# line_sensor.net
KiCad netlist of a schematic drawn in EAGLE
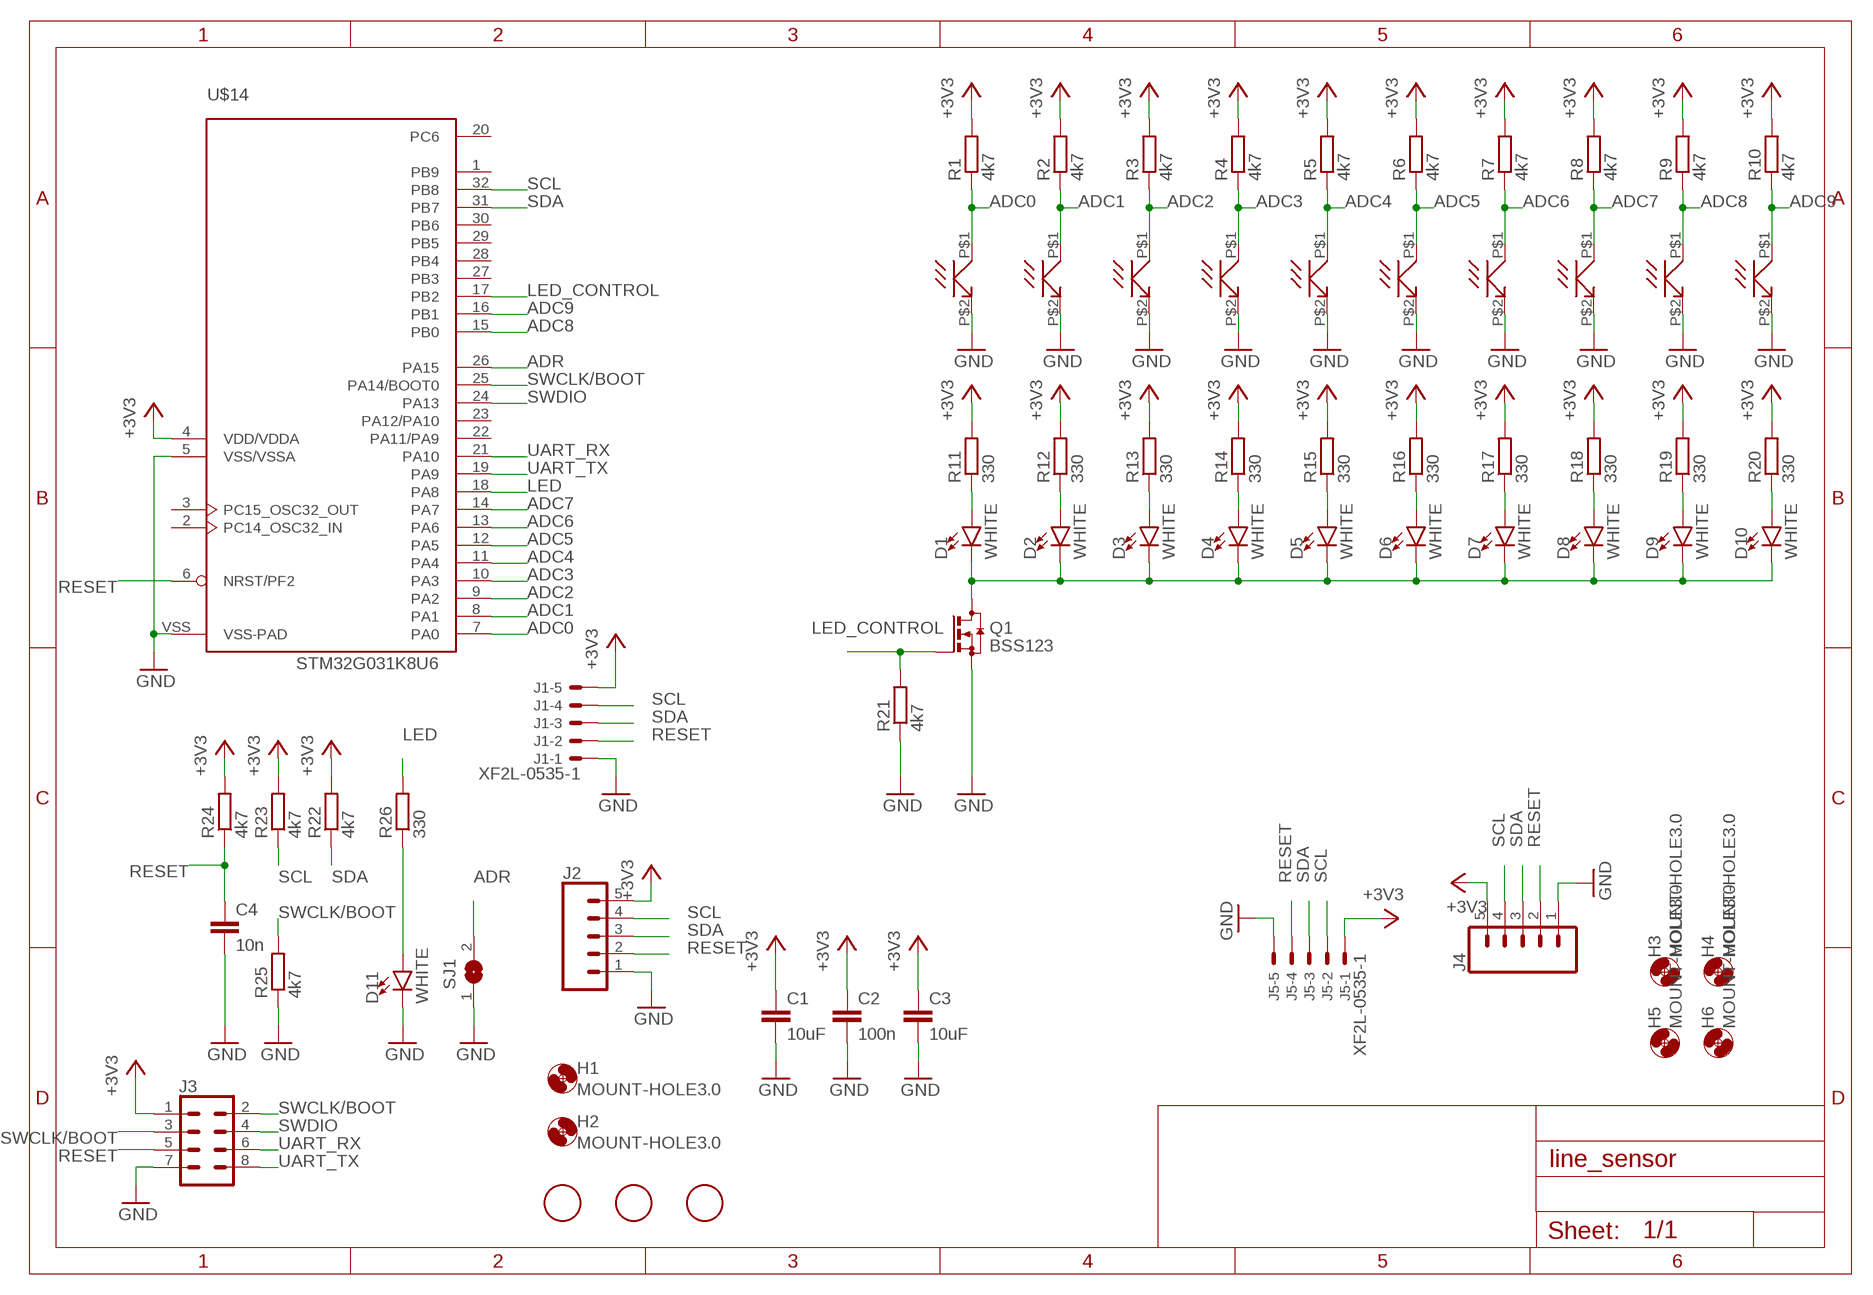
[diagram p0: schematic, sheet 1]

(export (version "E")
  (design (tool "Eeschema 10.0.6"))
  (components
    (comp (ref "C1")
      (value "10uF")
      (footprint "eagle-import:C0805K")
      (libsource (lib "eagle-import") (part "C-EUC0805K"))
    )
    (comp (ref "C2")
      (value "100n")
      (footprint "eagle-import:C0805K")
      (libsource (lib "eagle-import") (part "C-EUC0805K"))
    )
    (comp (ref "C3")
      (value "10uF")
      (footprint "eagle-import:C0805K")
      (libsource (lib "eagle-import") (part "C-EUC0805K"))
    )
    (comp (ref "C4")
      (value "10n")
      (footprint "eagle-import:C0805K")
      (libsource (lib "eagle-import") (part "C-EUC0805K"))
    )
    (comp (ref "D1")
      (value "WHITE")
      (footprint "eagle-import:LED-1206")
      (libsource (lib "eagle-import") (part "LED-WHITE1206"))
    )
    (comp (ref "D2")
      (value "WHITE")
      (footprint "eagle-import:LED-1206")
      (libsource (lib "eagle-import") (part "LED-WHITE1206"))
    )
    (comp (ref "D3")
      (value "WHITE")
      (footprint "eagle-import:LED-1206")
      (libsource (lib "eagle-import") (part "LED-WHITE1206"))
    )
    (comp (ref "D4")
      (value "WHITE")
      (footprint "eagle-import:LED-1206")
      (libsource (lib "eagle-import") (part "LED-WHITE1206"))
    )
    (comp (ref "D5")
      (value "WHITE")
      (footprint "eagle-import:LED-1206")
      (libsource (lib "eagle-import") (part "LED-WHITE1206"))
    )
    (comp (ref "D6")
      (value "WHITE")
      (footprint "eagle-import:LED-1206")
      (libsource (lib "eagle-import") (part "LED-WHITE1206"))
    )
    (comp (ref "D7")
      (value "WHITE")
      (footprint "eagle-import:LED-1206")
      (libsource (lib "eagle-import") (part "LED-WHITE1206"))
    )
    (comp (ref "D8")
      (value "WHITE")
      (footprint "eagle-import:LED-1206")
      (libsource (lib "eagle-import") (part "LED-WHITE1206"))
    )
    (comp (ref "D9")
      (value "WHITE")
      (footprint "eagle-import:LED-1206")
      (libsource (lib "eagle-import") (part "LED-WHITE1206"))
    )
    (comp (ref "D10")
      (value "WHITE")
      (footprint "eagle-import:LED-1206")
      (libsource (lib "eagle-import") (part "LED-WHITE1206"))
    )
    (comp (ref "D11")
      (value "WHITE")
      (footprint "eagle-import:LED-1206")
      (libsource (lib "eagle-import") (part "LED-WHITE1206"))
    )
    (comp (ref "H1")
      (value "MOUNT-HOLE3.0")
      (footprint "eagle-import:3,0")
      (libsource (lib "eagle-import") (part "MOUNT-HOLE3.0"))
    )
    (comp (ref "H2")
      (value "MOUNT-HOLE3.0")
      (footprint "eagle-import:3,0")
      (libsource (lib "eagle-import") (part "MOUNT-HOLE3.0"))
    )
    (comp (ref "H3")
      (value "MOUNT-HOLE3.0")
      (footprint "eagle-import:3,0")
      (libsource (lib "eagle-import") (part "MOUNT-HOLE3.0"))
    )
    (comp (ref "H4")
      (value "MOUNT-HOLE3.0")
      (footprint "eagle-import:3,0")
      (libsource (lib "eagle-import") (part "MOUNT-HOLE3.0"))
    )
    (comp (ref "H5")
      (value "MOUNT-HOLE3.0")
      (footprint "eagle-import:3,0")
      (libsource (lib "eagle-import") (part "MOUNT-HOLE3.0"))
    )
    (comp (ref "H6")
      (value "MOUNT-HOLE3.0")
      (footprint "eagle-import:3,0")
      (libsource (lib "eagle-import") (part "MOUNT-HOLE3.0"))
    )
    (comp (ref "J1")
      (value "XF2L-0535-1")
      (footprint "eagle-import:XF2L-0535-1")
      (fields (field (name "MPN") "XF2L-0535-1A"))
      (libsource (lib "eagle-import") (part "XF2-05?35-1L"))
    )
    (comp (ref "J2")
      (value "CONN_05")
      (footprint "eagle-import:1X05")
      (libsource (lib "eagle-import") (part "CONN_05"))
    )
    (comp (ref "J3")
      (value "CONN_04X2")
      (footprint "eagle-import:2X4")
      (libsource (lib "eagle-import") (part "CONN_04X2"))
    )
    (comp (ref "J4")
      (value "CONN_05")
      (footprint "eagle-import:1X05")
      (libsource (lib "eagle-import") (part "CONN_05"))
    )
    (comp (ref "J5")
      (value "XF2L-0535-1")
      (footprint "eagle-import:XF2L-0535-1")
      (fields (field (name "MPN") "XF2L-0535-1A"))
      (libsource (lib "eagle-import") (part "XF2-05?35-1L"))
    )
    (comp (ref "Q1")
      (value "BSS123")
      (footprint "eagle-import:SOT23")
      (libsource (lib "eagle-import") (part "BSS123"))
    )
    (comp (ref "R1")
      (value "4k7")
      (footprint "eagle-import:M0805")
      (libsource (lib "eagle-import") (part "R-EU_M0805"))
    )
    (comp (ref "R2")
      (value "4k7")
      (footprint "eagle-import:M0805")
      (libsource (lib "eagle-import") (part "R-EU_M0805"))
    )
    (comp (ref "R3")
      (value "4k7")
      (footprint "eagle-import:M0805")
      (libsource (lib "eagle-import") (part "R-EU_M0805"))
    )
    (comp (ref "R4")
      (value "4k7")
      (footprint "eagle-import:M0805")
      (libsource (lib "eagle-import") (part "R-EU_M0805"))
    )
    (comp (ref "R5")
      (value "4k7")
      (footprint "eagle-import:M0805")
      (libsource (lib "eagle-import") (part "R-EU_M0805"))
    )
    (comp (ref "R6")
      (value "4k7")
      (footprint "eagle-import:M0805")
      (libsource (lib "eagle-import") (part "R-EU_M0805"))
    )
    (comp (ref "R7")
      (value "4k7")
      (footprint "eagle-import:M0805")
      (libsource (lib "eagle-import") (part "R-EU_M0805"))
    )
    (comp (ref "R8")
      (value "4k7")
      (footprint "eagle-import:M0805")
      (libsource (lib "eagle-import") (part "R-EU_M0805"))
    )
    (comp (ref "R9")
      (value "4k7")
      (footprint "eagle-import:M0805")
      (libsource (lib "eagle-import") (part "R-EU_M0805"))
    )
    (comp (ref "R10")
      (value "4k7")
      (footprint "eagle-import:M0805")
      (libsource (lib "eagle-import") (part "R-EU_M0805"))
    )
    (comp (ref "R11")
      (value "330")
      (footprint "eagle-import:M0805")
      (libsource (lib "eagle-import") (part "R-EU_M0805"))
    )
    (comp (ref "R12")
      (value "330")
      (footprint "eagle-import:M0805")
      (libsource (lib "eagle-import") (part "R-EU_M0805"))
    )
    (comp (ref "R13")
      (value "330")
      (footprint "eagle-import:M0805")
      (libsource (lib "eagle-import") (part "R-EU_M0805"))
    )
    (comp (ref "R14")
      (value "330")
      (footprint "eagle-import:M0805")
      (libsource (lib "eagle-import") (part "R-EU_M0805"))
    )
    (comp (ref "R15")
      (value "330")
      (footprint "eagle-import:M0805")
      (libsource (lib "eagle-import") (part "R-EU_M0805"))
    )
    (comp (ref "R16")
      (value "330")
      (footprint "eagle-import:M0805")
      (libsource (lib "eagle-import") (part "R-EU_M0805"))
    )
    (comp (ref "R17")
      (value "330")
      (footprint "eagle-import:M0805")
      (libsource (lib "eagle-import") (part "R-EU_M0805"))
    )
    (comp (ref "R18")
      (value "330")
      (footprint "eagle-import:M0805")
      (libsource (lib "eagle-import") (part "R-EU_M0805"))
    )
    (comp (ref "R19")
      (value "330")
      (footprint "eagle-import:M0805")
      (libsource (lib "eagle-import") (part "R-EU_M0805"))
    )
    (comp (ref "R20")
      (value "330")
      (footprint "eagle-import:M0805")
      (libsource (lib "eagle-import") (part "R-EU_M0805"))
    )
    (comp (ref "R21")
      (value "4k7")
      (footprint "eagle-import:M0805")
      (libsource (lib "eagle-import") (part "R-EU_M0805"))
    )
    (comp (ref "R22")
      (value "4k7")
      (footprint "eagle-import:M0805")
      (libsource (lib "eagle-import") (part "R-EU_M0805"))
    )
    (comp (ref "R23")
      (value "4k7")
      (footprint "eagle-import:M0805")
      (libsource (lib "eagle-import") (part "R-EU_M0805"))
    )
    (comp (ref "R24")
      (value "4k7")
      (footprint "eagle-import:M0805")
      (libsource (lib "eagle-import") (part "R-EU_M0805"))
    )
    (comp (ref "R25")
      (value "4k7")
      (footprint "eagle-import:M0805")
      (libsource (lib "eagle-import") (part "R-EU_M0805"))
    )
    (comp (ref "R26")
      (value "330")
      (footprint "eagle-import:M0805")
      (libsource (lib "eagle-import") (part "R-EU_M0805"))
    )
    (comp (ref "SJ1") (value "SJ") (footprint "eagle-import:SJ") (libsource (lib "eagle-import") (part "SJ")))
    (comp (ref "U$1")
      (value "SFH3710")
      (footprint "eagle-import:SFH710")
      (libsource (lib "eagle-import") (part "SFH3710"))
    )
    (comp (ref "U$2")
      (value "SFH3710")
      (footprint "eagle-import:SFH710")
      (libsource (lib "eagle-import") (part "SFH3710"))
    )
    (comp (ref "U$3")
      (value "SFH3710")
      (footprint "eagle-import:SFH710")
      (libsource (lib "eagle-import") (part "SFH3710"))
    )
    (comp (ref "U$4")
      (value "SFH3710")
      (footprint "eagle-import:SFH710")
      (libsource (lib "eagle-import") (part "SFH3710"))
    )
    (comp (ref "U$5")
      (value "SFH3710")
      (footprint "eagle-import:SFH710")
      (libsource (lib "eagle-import") (part "SFH3710"))
    )
    (comp (ref "U$6")
      (value "SFH3710")
      (footprint "eagle-import:SFH710")
      (libsource (lib "eagle-import") (part "SFH3710"))
    )
    (comp (ref "U$7")
      (value "SFH3710")
      (footprint "eagle-import:SFH710")
      (libsource (lib "eagle-import") (part "SFH3710"))
    )
    (comp (ref "U$8")
      (value "SFH3710")
      (footprint "eagle-import:SFH710")
      (libsource (lib "eagle-import") (part "SFH3710"))
    )
    (comp (ref "U$9")
      (value "SFH3710")
      (footprint "eagle-import:SFH710")
      (libsource (lib "eagle-import") (part "SFH3710"))
    )
    (comp (ref "U$10")
      (value "SFH3710")
      (footprint "eagle-import:SFH710")
      (libsource (lib "eagle-import") (part "SFH3710"))
    )
    (comp (ref "U$11")
      (value "FIDUCIAL")
      (footprint "eagle-import:FIDUCIAL_1MM")
      (libsource (lib "eagle-import") (part "FIDUCIAL"))
    )
    (comp (ref "U$12")
      (value "FIDUCIAL")
      (footprint "eagle-import:FIDUCIAL_1MM")
      (libsource (lib "eagle-import") (part "FIDUCIAL"))
    )
    (comp (ref "U$13")
      (value "FIDUCIAL")
      (footprint "eagle-import:FIDUCIAL_1MM")
      (libsource (lib "eagle-import") (part "FIDUCIAL"))
    )
    (comp (ref "U$14")
      (value "STM32G031K8U6")
      (footprint "eagle-import:UFQFPN32")
      (libsource (lib "eagle-import") (part "STM32G031K8U6"))
    )
  )
  (nets
    (net (code "1") (name "+3V3") (class "Default")
      (node (ref "C1") (pin "1") (pinfunction "1_1") (pintype "passive"))
      (node (ref "C2") (pin "1") (pinfunction "1_1") (pintype "passive"))
      (node (ref "C3") (pin "1") (pinfunction "1_1") (pintype "passive"))
      (node (ref "J1") (pin "5") (pinfunction "MS_5") (pintype "passive"))
      (node (ref "J2") (pin "5") (pinfunction "5_5") (pintype "passive"))
      (node (ref "J3") (pin "1") (pinfunction "1_1") (pintype "passive"))
      (node (ref "J4") (pin "5") (pinfunction "5_5") (pintype "passive"))
      (node (ref "J5") (pin "1") (pinfunction "MSV_1") (pintype "passive"))
      (node (ref "R1") (pin "2") (pinfunction "2_2") (pintype "passive"))
      (node (ref "R10") (pin "2") (pinfunction "2_2") (pintype "passive"))
      (node (ref "R11") (pin "2") (pinfunction "2_2") (pintype "passive"))
      (node (ref "R12") (pin "2") (pinfunction "2_2") (pintype "passive"))
      (node (ref "R13") (pin "2") (pinfunction "2_2") (pintype "passive"))
      (node (ref "R14") (pin "2") (pinfunction "2_2") (pintype "passive"))
      (node (ref "R15") (pin "2") (pinfunction "2_2") (pintype "passive"))
      (node (ref "R16") (pin "2") (pinfunction "2_2") (pintype "passive"))
      (node (ref "R17") (pin "2") (pinfunction "2_2") (pintype "passive"))
      (node (ref "R18") (pin "2") (pinfunction "2_2") (pintype "passive"))
      (node (ref "R19") (pin "2") (pinfunction "2_2") (pintype "passive"))
      (node (ref "R2") (pin "2") (pinfunction "2_2") (pintype "passive"))
      (node (ref "R20") (pin "2") (pinfunction "2_2") (pintype "passive"))
      (node (ref "R22") (pin "2") (pinfunction "2_2") (pintype "passive"))
      (node (ref "R23") (pin "2") (pinfunction "2_2") (pintype "passive"))
      (node (ref "R24") (pin "2") (pinfunction "2_2") (pintype "passive"))
      (node (ref "R3") (pin "2") (pinfunction "2_2") (pintype "passive"))
      (node (ref "R4") (pin "2") (pinfunction "2_2") (pintype "passive"))
      (node (ref "R5") (pin "2") (pinfunction "2_2") (pintype "passive"))
      (node (ref "R6") (pin "2") (pinfunction "2_2") (pintype "passive"))
      (node (ref "R7") (pin "2") (pinfunction "2_2") (pintype "passive"))
      (node (ref "R8") (pin "2") (pinfunction "2_2") (pintype "passive"))
      (node (ref "R9") (pin "2") (pinfunction "2_2") (pintype "passive"))
      (node (ref "U$14") (pin "4") (pinfunction "VDD/VDDA_4") (pintype "power_in"))
    )
    (net (code "2") (name "/ADC0") (class "Default")
      (node (ref "R1") (pin "1") (pinfunction "1_1") (pintype "passive"))
      (node (ref "U$1") (pin "P$1") (pinfunction "C_P$1") (pintype "bidirectional"))
      (node (ref "U$14") (pin "7") (pinfunction "PA0_7") (pintype "bidirectional"))
    )
    (net (code "3") (name "/ADC1") (class "Default")
      (node (ref "R2") (pin "1") (pinfunction "1_1") (pintype "passive"))
      (node (ref "U$14") (pin "8") (pinfunction "PA1_8") (pintype "bidirectional"))
      (node (ref "U$2") (pin "P$1") (pinfunction "C_P$1") (pintype "bidirectional"))
    )
    (net (code "4") (name "/ADC2") (class "Default")
      (node (ref "R3") (pin "1") (pinfunction "1_1") (pintype "passive"))
      (node (ref "U$14") (pin "9") (pinfunction "PA2_9") (pintype "bidirectional"))
      (node (ref "U$3") (pin "P$1") (pinfunction "C_P$1") (pintype "bidirectional"))
    )
    (net (code "5") (name "/ADC3") (class "Default")
      (node (ref "R4") (pin "1") (pinfunction "1_1") (pintype "passive"))
      (node (ref "U$14") (pin "10") (pinfunction "PA3_10") (pintype "bidirectional"))
      (node (ref "U$4") (pin "P$1") (pinfunction "C_P$1") (pintype "bidirectional"))
    )
    (net (code "6") (name "/ADC4") (class "Default")
      (node (ref "R5") (pin "1") (pinfunction "1_1") (pintype "passive"))
      (node (ref "U$14") (pin "11") (pinfunction "PA4_11") (pintype "bidirectional"))
      (node (ref "U$5") (pin "P$1") (pinfunction "C_P$1") (pintype "bidirectional"))
    )
    (net (code "7") (name "/ADC5") (class "Default")
      (node (ref "R6") (pin "1") (pinfunction "1_1") (pintype "passive"))
      (node (ref "U$14") (pin "12") (pinfunction "PA5_12") (pintype "bidirectional"))
      (node (ref "U$6") (pin "P$1") (pinfunction "C_P$1") (pintype "bidirectional"))
    )
    (net (code "8") (name "/ADC6") (class "Default")
      (node (ref "R7") (pin "1") (pinfunction "1_1") (pintype "passive"))
      (node (ref "U$14") (pin "13") (pinfunction "PA6_13") (pintype "bidirectional"))
      (node (ref "U$7") (pin "P$1") (pinfunction "C_P$1") (pintype "bidirectional"))
    )
    (net (code "9") (name "/ADC7") (class "Default")
      (node (ref "R8") (pin "1") (pinfunction "1_1") (pintype "passive"))
      (node (ref "U$14") (pin "14") (pinfunction "PA7_14") (pintype "bidirectional"))
      (node (ref "U$8") (pin "P$1") (pinfunction "C_P$1") (pintype "bidirectional"))
    )
    (net (code "10") (name "/ADC8") (class "Default")
      (node (ref "R9") (pin "1") (pinfunction "1_1") (pintype "passive"))
      (node (ref "U$14") (pin "15") (pinfunction "PB0_15") (pintype "bidirectional"))
      (node (ref "U$9") (pin "P$1") (pinfunction "C_P$1") (pintype "bidirectional"))
    )
    (net (code "11") (name "/ADC9") (class "Default")
      (node (ref "R10") (pin "1") (pinfunction "1_1") (pintype "passive"))
      (node (ref "U$10") (pin "P$1") (pinfunction "C_P$1") (pintype "bidirectional"))
      (node (ref "U$14") (pin "16") (pinfunction "PB1_16") (pintype "bidirectional"))
    )
    (net (code "12") (name "/ADR") (class "Default")
      (node (ref "SJ1") (pin "2") (pinfunction "2_2") (pintype "passive"))
      (node (ref "U$14") (pin "26") (pinfunction "PA15_26") (pintype "bidirectional"))
    )
    (net (code "13") (name "/LED") (class "Default")
      (node (ref "R26") (pin "2") (pinfunction "2_2") (pintype "passive"))
      (node (ref "U$14") (pin "18") (pinfunction "PA8_18") (pintype "bidirectional"))
    )
    (net (code "14") (name "/LED_CONTROL") (class "Default")
      (node (ref "Q1") (pin "1") (pinfunction "G_1") (pintype "passive"))
      (node (ref "R21") (pin "2") (pinfunction "2_2") (pintype "passive"))
      (node (ref "U$14") (pin "17") (pinfunction "PB2_17") (pintype "bidirectional"))
    )
    (net (code "15") (name "/RESET") (class "Default")
      (node (ref "C4") (pin "1") (pinfunction "1_1") (pintype "passive"))
      (node (ref "J1") (pin "2") (pinfunction "MS_2") (pintype "passive"))
      (node (ref "J2") (pin "2") (pinfunction "2_2") (pintype "passive"))
      (node (ref "J3") (pin "5") (pinfunction "5_5") (pintype "passive"))
      (node (ref "J4") (pin "2") (pinfunction "2_2") (pintype "passive"))
      (node (ref "J5") (pin "4") (pinfunction "MS_4") (pintype "passive"))
      (node (ref "R24") (pin "1") (pinfunction "1_1") (pintype "passive"))
      (node (ref "U$14") (pin "6") (pinfunction "NRST/PF2_6") (pintype "bidirectional"))
    )
    (net (code "16") (name "/SCL") (class "Default")
      (node (ref "J1") (pin "4") (pinfunction "MS_4") (pintype "passive"))
      (node (ref "J2") (pin "4") (pinfunction "4_4") (pintype "passive"))
      (node (ref "J4") (pin "4") (pinfunction "4_4") (pintype "passive"))
      (node (ref "J5") (pin "2") (pinfunction "MS_2") (pintype "passive"))
      (node (ref "R23") (pin "1") (pinfunction "1_1") (pintype "passive"))
      (node (ref "U$14") (pin "32") (pinfunction "PB8_32") (pintype "bidirectional"))
    )
    (net (code "17") (name "/SDA") (class "Default")
      (node (ref "J1") (pin "3") (pinfunction "MS_3") (pintype "passive"))
      (node (ref "J2") (pin "3") (pinfunction "3_3") (pintype "passive"))
      (node (ref "J4") (pin "3") (pinfunction "3_3") (pintype "passive"))
      (node (ref "J5") (pin "3") (pinfunction "MS_3") (pintype "passive"))
      (node (ref "R22") (pin "1") (pinfunction "1_1") (pintype "passive"))
      (node (ref "U$14") (pin "31") (pinfunction "PB7_31") (pintype "bidirectional"))
    )
    (net (code "18") (name "/SWCLK{slash}BOOT") (class "Default")
      (node (ref "J3") (pin "2") (pinfunction "2_2") (pintype "passive"))
      (node (ref "J3") (pin "3") (pinfunction "3_3") (pintype "passive"))
      (node (ref "R25") (pin "2") (pinfunction "2_2") (pintype "passive"))
      (node (ref "U$14") (pin "25") (pinfunction "PA14/BOOT0_25") (pintype "bidirectional"))
    )
    (net (code "19") (name "/SWDIO") (class "Default")
      (node (ref "J3") (pin "4") (pinfunction "4_4") (pintype "passive"))
      (node (ref "U$14") (pin "24") (pinfunction "PA13_24") (pintype "bidirectional"))
    )
    (net (code "20") (name "/UART_RX") (class "Default")
      (node (ref "J3") (pin "6") (pinfunction "6_6") (pintype "passive"))
      (node (ref "U$14") (pin "21") (pinfunction "PA10_21") (pintype "bidirectional"))
    )
    (net (code "21") (name "/UART_TX") (class "Default")
      (node (ref "J3") (pin "8") (pinfunction "8_8") (pintype "passive"))
      (node (ref "U$14") (pin "19") (pinfunction "PA9_19") (pintype "bidirectional"))
    )
    (net (code "22") (name "GND") (class "Default")
      (node (ref "C1") (pin "2") (pinfunction "2_2") (pintype "passive"))
      (node (ref "C2") (pin "2") (pinfunction "2_2") (pintype "passive"))
      (node (ref "C3") (pin "2") (pinfunction "2_2") (pintype "passive"))
      (node (ref "C4") (pin "2") (pinfunction "2_2") (pintype "passive"))
      (node (ref "D11") (pin "C") (pinfunction "C_C") (pintype "passive"))
      (node (ref "J1") (pin "1") (pinfunction "MSV_1") (pintype "passive"))
      (node (ref "J2") (pin "1") (pinfunction "1_1") (pintype "passive"))
      (node (ref "J3") (pin "7") (pinfunction "7_7") (pintype "passive"))
      (node (ref "J4") (pin "1") (pinfunction "1_1") (pintype "passive"))
      (node (ref "J5") (pin "5") (pinfunction "MS_5") (pintype "passive"))
      (node (ref "Q1") (pin "2") (pinfunction "S_2") (pintype "passive"))
      (node (ref "R21") (pin "1") (pinfunction "1_1") (pintype "passive"))
      (node (ref "R25") (pin "1") (pinfunction "1_1") (pintype "passive"))
      (node (ref "SJ1") (pin "1") (pinfunction "1_1") (pintype "passive"))
      (node (ref "U$1") (pin "P$2") (pinfunction "E_P$2") (pintype "bidirectional"))
      (node (ref "U$10") (pin "P$2") (pinfunction "E_P$2") (pintype "bidirectional"))
      (node (ref "U$14") (pin "5") (pinfunction "VSS/VSSA_5") (pintype "power_in"))
      (node (ref "U$14") (pin "VSS") (pinfunction "VSS-PAD_VSS") (pintype "bidirectional"))
      (node (ref "U$2") (pin "P$2") (pinfunction "E_P$2") (pintype "bidirectional"))
      (node (ref "U$3") (pin "P$2") (pinfunction "E_P$2") (pintype "bidirectional"))
      (node (ref "U$4") (pin "P$2") (pinfunction "E_P$2") (pintype "bidirectional"))
      (node (ref "U$5") (pin "P$2") (pinfunction "E_P$2") (pintype "bidirectional"))
      (node (ref "U$6") (pin "P$2") (pinfunction "E_P$2") (pintype "bidirectional"))
      (node (ref "U$7") (pin "P$2") (pinfunction "E_P$2") (pintype "bidirectional"))
      (node (ref "U$8") (pin "P$2") (pinfunction "E_P$2") (pintype "bidirectional"))
      (node (ref "U$9") (pin "P$2") (pinfunction "E_P$2") (pintype "bidirectional"))
    )
    (net (code "23") (name "Net-(D1-PadA)") (class "Default")
      (node (ref "D1") (pin "A") (pinfunction "A_A") (pintype "passive"))
      (node (ref "R11") (pin "1") (pinfunction "1_1") (pintype "passive"))
    )
    (net (code "24") (name "Net-(D2-PadA)") (class "Default")
      (node (ref "D2") (pin "A") (pinfunction "A_A") (pintype "passive"))
      (node (ref "R12") (pin "1") (pinfunction "1_1") (pintype "passive"))
    )
    (net (code "25") (name "Net-(D3-PadA)") (class "Default")
      (node (ref "D3") (pin "A") (pinfunction "A_A") (pintype "passive"))
      (node (ref "R13") (pin "1") (pinfunction "1_1") (pintype "passive"))
    )
    (net (code "26") (name "Net-(D4-PadA)") (class "Default")
      (node (ref "D4") (pin "A") (pinfunction "A_A") (pintype "passive"))
      (node (ref "R14") (pin "1") (pinfunction "1_1") (pintype "passive"))
    )
    (net (code "27") (name "Net-(D5-PadA)") (class "Default")
      (node (ref "D5") (pin "A") (pinfunction "A_A") (pintype "passive"))
      (node (ref "R15") (pin "1") (pinfunction "1_1") (pintype "passive"))
    )
    (net (code "28") (name "Net-(D6-PadA)") (class "Default")
      (node (ref "D6") (pin "A") (pinfunction "A_A") (pintype "passive"))
      (node (ref "R16") (pin "1") (pinfunction "1_1") (pintype "passive"))
    )
    (net (code "29") (name "Net-(D7-PadA)") (class "Default")
      (node (ref "D7") (pin "A") (pinfunction "A_A") (pintype "passive"))
      (node (ref "R17") (pin "1") (pinfunction "1_1") (pintype "passive"))
    )
    (net (code "30") (name "Net-(D8-PadA)") (class "Default")
      (node (ref "D8") (pin "A") (pinfunction "A_A") (pintype "passive"))
      (node (ref "R18") (pin "1") (pinfunction "1_1") (pintype "passive"))
    )
    (net (code "31") (name "Net-(D9-PadA)") (class "Default")
      (node (ref "D9") (pin "A") (pinfunction "A_A") (pintype "passive"))
      (node (ref "R19") (pin "1") (pinfunction "1_1") (pintype "passive"))
    )
    (net (code "32") (name "Net-(D10-PadA)") (class "Default")
      (node (ref "D10") (pin "A") (pinfunction "A_A") (pintype "passive"))
      (node (ref "R20") (pin "1") (pinfunction "1_1") (pintype "passive"))
    )
    (net (code "33") (name "Net-(D11-PadA)") (class "Default")
      (node (ref "D11") (pin "A") (pinfunction "A_A") (pintype "passive"))
      (node (ref "R26") (pin "1") (pinfunction "1_1") (pintype "passive"))
    )
    (net (code "34") (name "Net-(Q1-D)") (class "Default")
      (node (ref "D1") (pin "C") (pinfunction "C_C") (pintype "passive"))
      (node (ref "D10") (pin "C") (pinfunction "C_C") (pintype "passive"))
      (node (ref "D2") (pin "C") (pinfunction "C_C") (pintype "passive"))
      (node (ref "D3") (pin "C") (pinfunction "C_C") (pintype "passive"))
      (node (ref "D4") (pin "C") (pinfunction "C_C") (pintype "passive"))
      (node (ref "D5") (pin "C") (pinfunction "C_C") (pintype "passive"))
      (node (ref "D6") (pin "C") (pinfunction "C_C") (pintype "passive"))
      (node (ref "D7") (pin "C") (pinfunction "C_C") (pintype "passive"))
      (node (ref "D8") (pin "C") (pinfunction "C_C") (pintype "passive"))
      (node (ref "D9") (pin "C") (pinfunction "C_C") (pintype "passive"))
      (node (ref "Q1") (pin "3") (pinfunction "D_3") (pintype "passive"))
    )
    (net (code "35") (name "unconnected-(U$14-PA11{slash}PA9-Pad22)") (class "Default")
      (node (ref "U$14") (pin "22") (pinfunction "PA11/PA9_22") (pintype "bidirectional"))
    )
    (net (code "36") (name "unconnected-(U$14-PA12{slash}PA10-Pad23)") (class "Default")
      (node (ref "U$14") (pin "23") (pinfunction "PA12/PA10_23") (pintype "bidirectional"))
    )
    (net (code "37") (name "unconnected-(U$14-PB3-Pad27)") (class "Default")
      (node (ref "U$14") (pin "27") (pinfunction "PB3_27") (pintype "bidirectional"))
    )
    (net (code "38") (name "unconnected-(U$14-PB4-Pad28)") (class "Default")
      (node (ref "U$14") (pin "28") (pinfunction "PB4_28") (pintype "bidirectional"))
    )
    (net (code "39") (name "unconnected-(U$14-PB5-Pad29)") (class "Default")
      (node (ref "U$14") (pin "29") (pinfunction "PB5_29") (pintype "bidirectional"))
    )
    (net (code "40") (name "unconnected-(U$14-PB6-Pad30)") (class "Default")
      (node (ref "U$14") (pin "30") (pinfunction "PB6_30") (pintype "bidirectional"))
    )
    (net (code "41") (name "unconnected-(U$14-PB9-Pad1)") (class "Default")
      (node (ref "U$14") (pin "1") (pinfunction "PB9_1") (pintype "bidirectional"))
    )
    (net (code "42") (name "unconnected-(U$14-PC6-Pad20)") (class "Default")
      (node (ref "U$14") (pin "20") (pinfunction "PC6_20") (pintype "bidirectional"))
    )
    (net (code "43") (name "unconnected-(U$14-PC14_OSC32_IN-Pad2)") (class "Default")
      (node (ref "U$14") (pin "2") (pinfunction "PC14_OSC32_IN_2") (pintype "bidirectional"))
    )
    (net (code "44") (name "unconnected-(U$14-PC15_OSC32_OUT-Pad3)") (class "Default")
      (node (ref "U$14") (pin "3") (pinfunction "PC15_OSC32_OUT_3") (pintype "bidirectional"))
    )
  )
)
